# 1_STM32_Tutorial-Power.net
KiCad netlist of a schematic drawn in Altium Designer
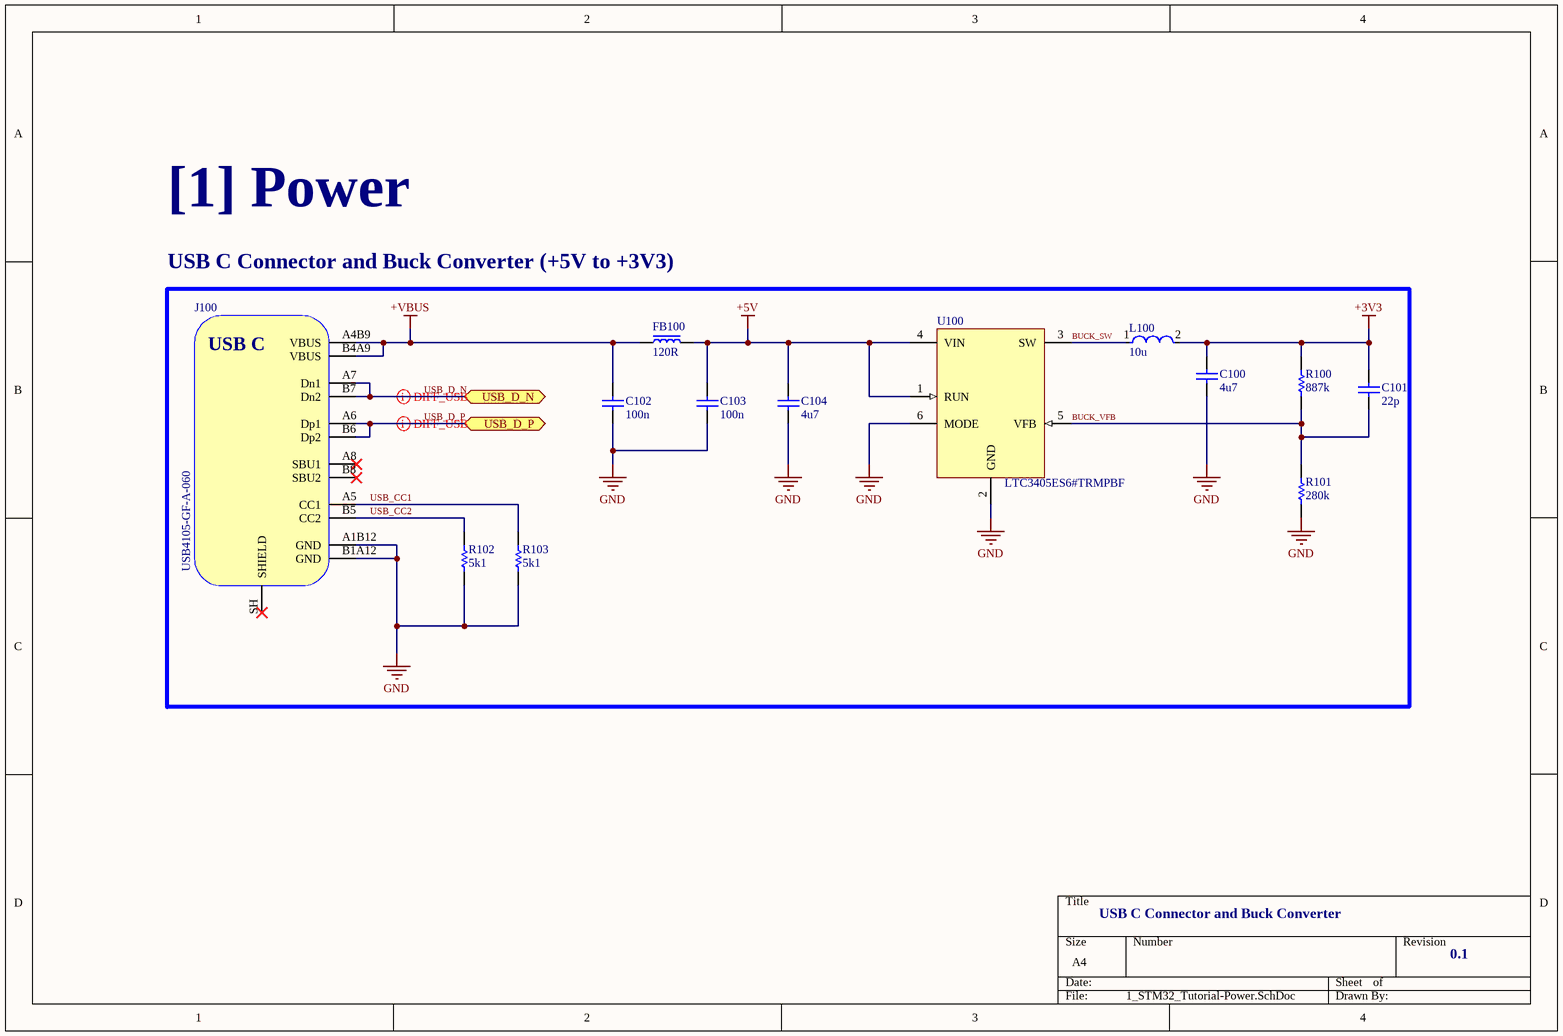
[diagram p0: 1_STM32_Tutorial-Power.SchDoc]

(export (version "E")
  (design (tool "Eeschema 10.0.6"))
  (components
    (comp (ref "C100")
      (value "4u7")
      (footprint "CAP_0805")
      (description "Capacitor SMD 0805 Generic")
      (libsource (lib "AndreiLib") (part "CAP_0805"))
    )
    (comp (ref "C101")
      (value "22p")
      (footprint "CAP_0603")
      (description "Capacitor SMD 0603 Generic")
      (libsource (lib "AndreiLib") (part "CAP_0603"))
    )
    (comp (ref "C102")
      (value "100n")
      (footprint "CAP_0603")
      (description "Capacitor SMD 0603 Generic")
      (libsource (lib "AndreiLib") (part "CAP_0603"))
    )
    (comp (ref "C103")
      (value "100n")
      (footprint "CAP_0603")
      (description "Capacitor SMD 0603 Generic")
      (libsource (lib "AndreiLib") (part "CAP_0603"))
    )
    (comp (ref "C104")
      (value "4u7")
      (footprint "CAP_0805")
      (description "Capacitor SMD 0805 Generic")
      (libsource (lib "AndreiLib") (part "CAP_0805"))
    )
    (comp (ref "FB100")
      (value "120R")
      (footprint "KMZ1608DHR121CTDH5")
      (description "Ferrite Beads 120MHz 0.3Ohm 25% 1608 AEC-Q200")
      (libsource (lib "AndreiLib") (part "KMZ1608DHR121CTDH5"))
    )
    (comp (ref "J100")
      (value "USB4105-GF-A-060")
      (footprint "USB4105-GF-A-060")
      (description "USB Connector Type C SMT 12 Pin")
      (libsource (lib "AndreiLib") (part "USB4105-GF-A-060"))
    )
    (comp (ref "L100")
      (value "10u")
      (footprint "FP-NRH2412-MFG")
      (description "NRH2412T100MNGH - Shielded Wirewound Inductor 10uH 20% 0.51A 0.72Ω SMD")
      (fields (field (name "TOLERANCE") "20%"))
      (libsource (lib "Altium Content Vault") (part "725321dda6339637d4d059423bc1c3c"))
    )
    (comp (ref "R100")
      (value "887k")
      (footprint "RES_0603")
      (description "Resistor SMD 0603 Generic")
      (libsource (lib "AndreiLib") (part "RES_0603"))
    )
    (comp (ref "R101")
      (value "280k")
      (footprint "RES_0603")
      (description "Resistor SMD 0603 Generic")
      (libsource (lib "AndreiLib") (part "RES_0603"))
    )
    (comp (ref "R102")
      (value "5k1")
      (footprint "RES_0603")
      (description "Resistor SMD 0603 Generic")
      (libsource (lib "AndreiLib") (part "RES_0603"))
    )
    (comp (ref "R103")
      (value "5k1")
      (footprint "RES_0603")
      (description "Resistor SMD 0603 Generic")
      (libsource (lib "AndreiLib") (part "RES_0603"))
    )
    (comp (ref "U100")
      (value "LTC3405ES6#TRMPBF")
      (footprint "SOT-23-6")
      (description "1.5MHz, 300mA Synchronous Step-Down Regulator in ThinSOT")
      (fields (field (name "MANUFACTURER") "Analog Devices"))
      (libsource (lib "AndreiLib") (part "LTC3405ES6#TRMPBF"))
    )
  )
  (nets
    (net (code "1") (name "+3V3") (class "Default")
      (node (ref "C100") (pin "1") (pintype "passive"))
      (node (ref "C101") (pin "2") (pintype "passive"))
      (node (ref "L100") (pin "2") (pinfunction "2_2") (pintype "passive"))
      (node (ref "R100") (pin "2") (pintype "passive"))
    )
    (net (code "2") (name "+5V") (class "Default")
      (node (ref "C103") (pin "2") (pintype "passive"))
      (node (ref "C104") (pin "1") (pintype "passive"))
      (node (ref "FB100") (pin "2") (pinfunction "2_2") (pintype "passive"))
      (node (ref "U100") (pin "1") (pinfunction "RUN_1") (pintype "input"))
      (node (ref "U100") (pin "4") (pinfunction "VIN_4") (pintype "power_in"))
    )
    (net (code "3") (name "+VBUS") (class "Default")
      (node (ref "C102") (pin "2") (pintype "passive"))
      (node (ref "FB100") (pin "1") (pinfunction "1_1") (pintype "passive"))
      (node (ref "J100") (pin "A4B9") (pinfunction "VBUS_A4B9") (pintype "passive"))
      (node (ref "J100") (pin "B4A9") (pinfunction "VBUS_B4A9") (pintype "passive"))
    )
    (net (code "4") (name "/BUCK_SW") (class "Default")
      (node (ref "L100") (pin "1") (pinfunction "1_1") (pintype "passive"))
      (node (ref "U100") (pin "3") (pinfunction "SW_3") (pintype "power_in"))
    )
    (net (code "5") (name "/BUCK_VFB") (class "Default")
      (node (ref "C101") (pin "1") (pintype "passive"))
      (node (ref "R100") (pin "1") (pintype "passive"))
      (node (ref "R101") (pin "2") (pintype "passive"))
      (node (ref "U100") (pin "5") (pinfunction "VFB_5") (pintype "input"))
    )
    (net (code "6") (name "/USB_CC1") (class "Default")
      (node (ref "J100") (pin "A5") (pinfunction "CC1_A5") (pintype "passive"))
      (node (ref "R103") (pin "2") (pintype "passive"))
    )
    (net (code "7") (name "/USB_CC2") (class "Default")
      (node (ref "J100") (pin "B5") (pinfunction "CC2_B5") (pintype "passive"))
      (node (ref "R102") (pin "2") (pintype "passive"))
    )
    (net (code "8") (name "/USB_D_N") (class "Default")
      (node (ref "J100") (pin "A7") (pinfunction "Dn1_A7") (pintype "passive"))
      (node (ref "J100") (pin "B7") (pinfunction "Dn2_B7") (pintype "passive"))
    )
    (net (code "9") (name "/USB_D_P") (class "Default")
      (node (ref "J100") (pin "A6") (pinfunction "Dp1_A6") (pintype "passive"))
      (node (ref "J100") (pin "B6") (pinfunction "Dp2_B6") (pintype "passive"))
    )
    (net (code "10") (name "GND") (class "Default")
      (node (ref "C100") (pin "2") (pintype "passive"))
      (node (ref "C102") (pin "1") (pintype "passive"))
      (node (ref "C103") (pin "1") (pintype "passive"))
      (node (ref "C104") (pin "2") (pintype "passive"))
      (node (ref "J100") (pin "A1B12") (pinfunction "GND_A1B12") (pintype "passive"))
      (node (ref "J100") (pin "B1A12") (pinfunction "GND_B1A12") (pintype "passive"))
      (node (ref "R101") (pin "1") (pintype "passive"))
      (node (ref "R102") (pin "1") (pintype "passive"))
      (node (ref "R103") (pin "1") (pintype "passive"))
      (node (ref "U100") (pin "2") (pinfunction "GND_2") (pintype "power_in"))
      (node (ref "U100") (pin "6") (pinfunction "MODE_6") (pintype "passive"))
    )
    (net (code "11") (name "unconnected-(J100-SBU1-PadA8)") (class "Default")
      (node (ref "J100") (pin "A8") (pinfunction "SBU1_A8") (pintype "passive+no_connect"))
    )
    (net (code "12") (name "unconnected-(J100-SBU2-PadB8)") (class "Default")
      (node (ref "J100") (pin "B8") (pinfunction "SBU2_B8") (pintype "passive+no_connect"))
    )
    (net (code "13") (name "unconnected-(J100-SHIELD-PadSH)") (class "Default")
      (node (ref "J100") (pin "SH") (pinfunction "SHIELD_SH") (pintype "passive+no_connect"))
    )
  )
)
